# Mars.net
KiCad netlist of a schematic drawn in EAGLE
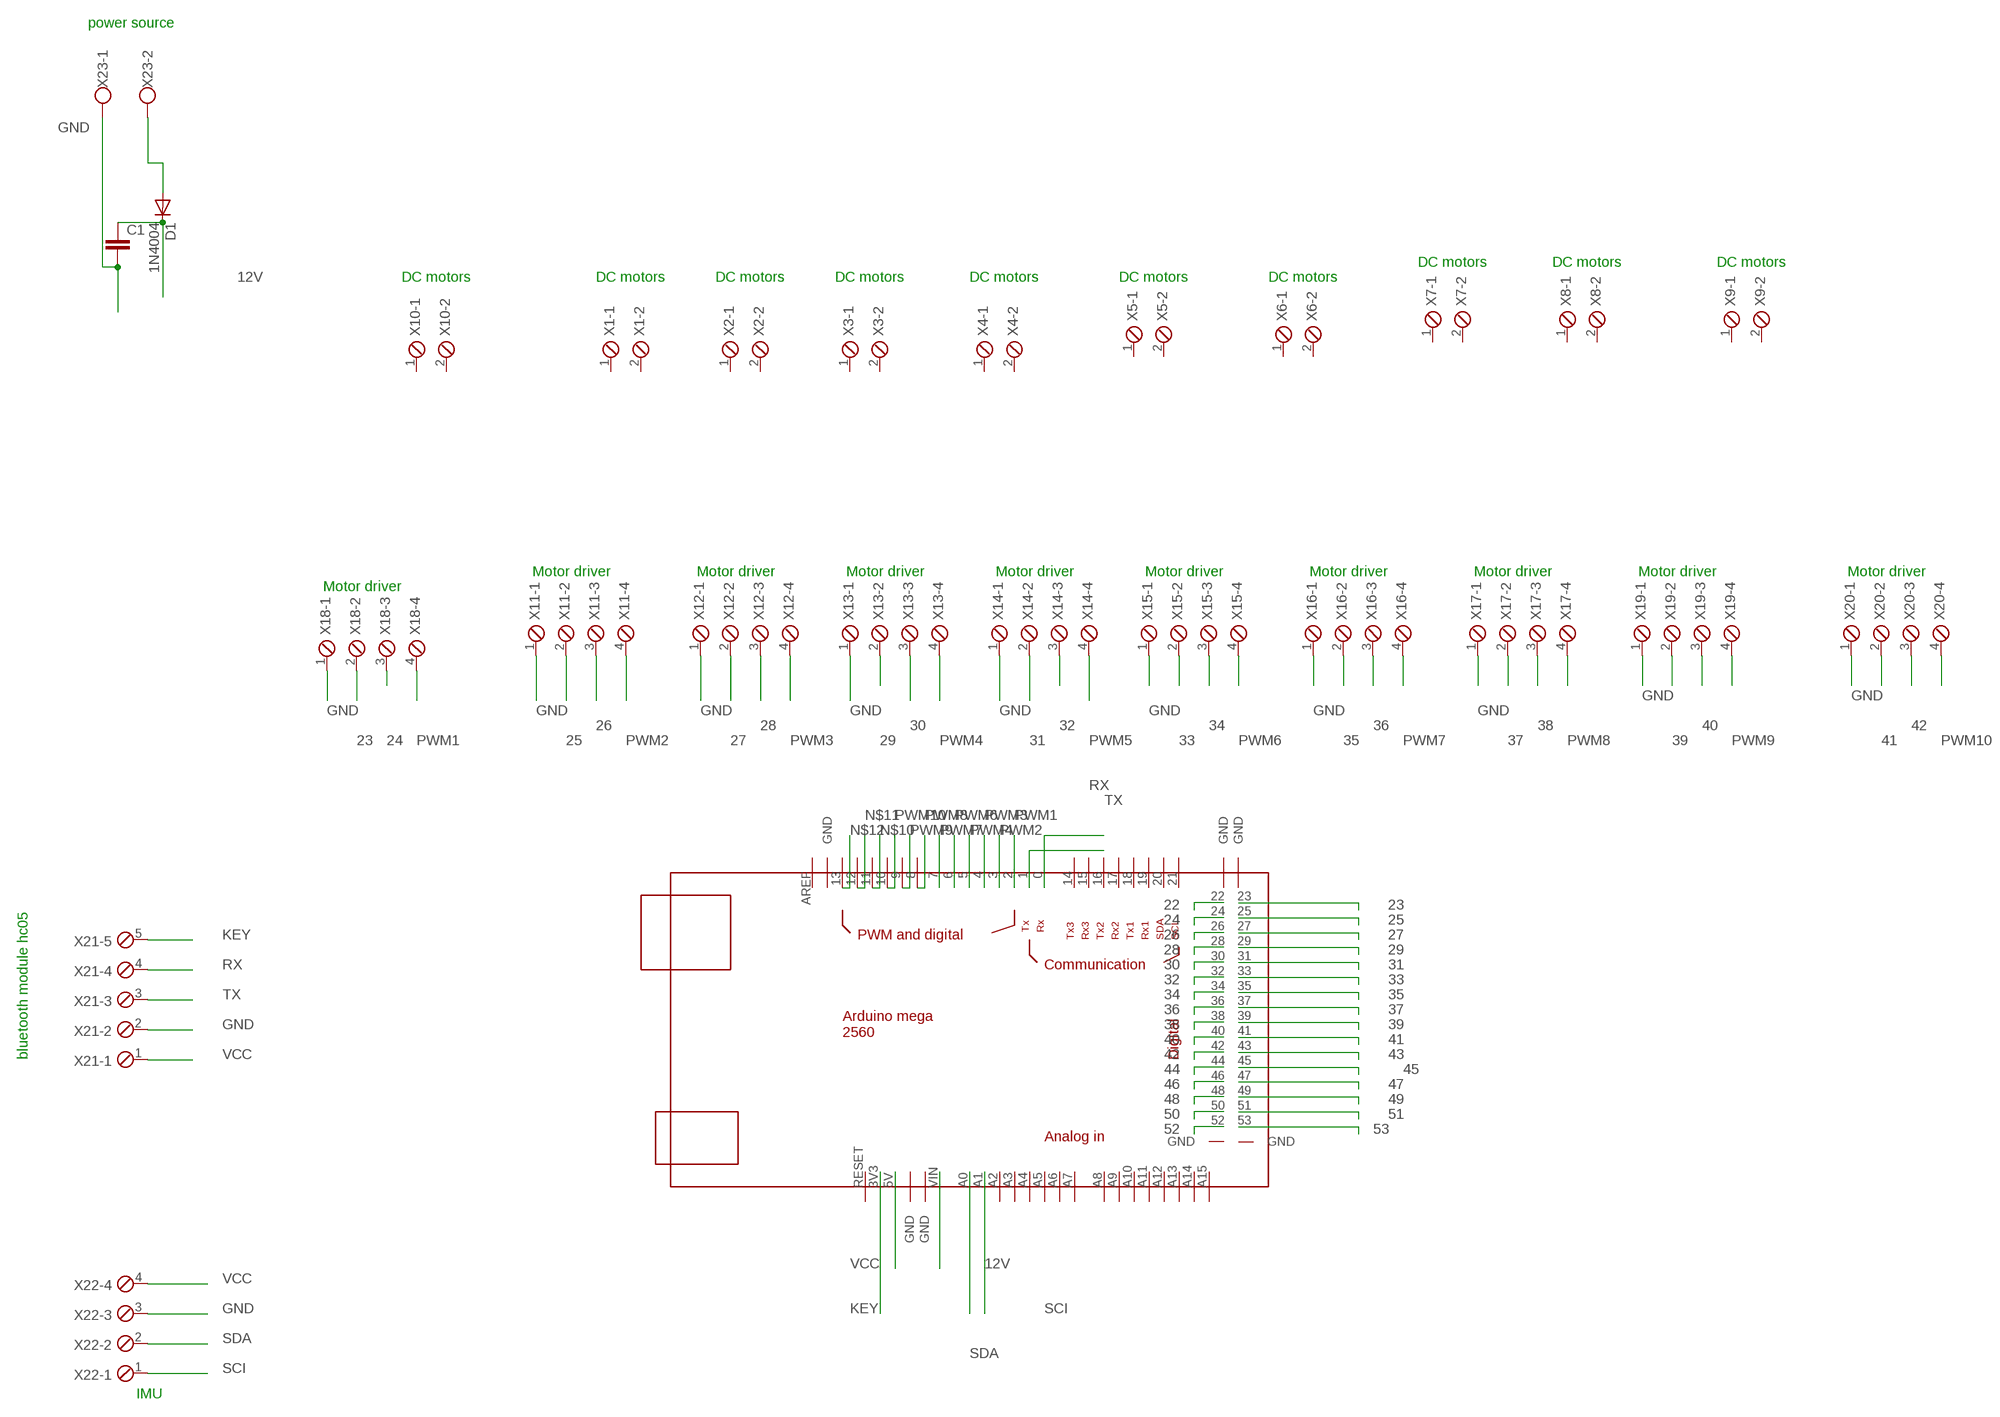
[diagram p0: schematic, sheet 1]

(export (version "E")
  (design (tool "Eeschema 10.0.6"))
  (components
    (comp (ref "C1")
      (value "C-EU025-025X050")
      (footprint "eagle-import:C025-025X050")
      (libsource (lib "eagle-import") (part "C-EU025-025X050"))
    )
    (comp (ref "D1")
      (value "1N4004")
      (footprint "eagle-import:DO41-10")
      (libsource (lib "eagle-import") (part "1N4004"))
    )
    (comp (ref "U$1")
      (value "MEGA_DEVICE")
      (footprint "eagle-import:MEGABOX")
      (libsource (lib "eagle-import") (part "MEGA_DEVICE"))
    )
    (comp (ref "X1")
      (value "MPT2")
      (footprint "eagle-import:2POL254")
      (libsource (lib "eagle-import") (part "MPT2"))
    )
    (comp (ref "X2")
      (value "MPT2")
      (footprint "eagle-import:2POL254")
      (libsource (lib "eagle-import") (part "MPT2"))
    )
    (comp (ref "X3")
      (value "MPT2")
      (footprint "eagle-import:2POL254")
      (libsource (lib "eagle-import") (part "MPT2"))
    )
    (comp (ref "X4")
      (value "MPT2")
      (footprint "eagle-import:2POL254")
      (libsource (lib "eagle-import") (part "MPT2"))
    )
    (comp (ref "X5")
      (value "MPT2")
      (footprint "eagle-import:2POL254")
      (libsource (lib "eagle-import") (part "MPT2"))
    )
    (comp (ref "X6")
      (value "MPT2")
      (footprint "eagle-import:2POL254")
      (libsource (lib "eagle-import") (part "MPT2"))
    )
    (comp (ref "X7")
      (value "MPT2")
      (footprint "eagle-import:2POL254")
      (libsource (lib "eagle-import") (part "MPT2"))
    )
    (comp (ref "X8")
      (value "MPT2")
      (footprint "eagle-import:2POL254")
      (libsource (lib "eagle-import") (part "MPT2"))
    )
    (comp (ref "X9")
      (value "MPT2")
      (footprint "eagle-import:2POL254")
      (libsource (lib "eagle-import") (part "MPT2"))
    )
    (comp (ref "X10")
      (value "MPT2")
      (footprint "eagle-import:2POL254")
      (libsource (lib "eagle-import") (part "MPT2"))
    )
    (comp (ref "X11")
      (value "MPT4")
      (footprint "eagle-import:4POL254")
      (libsource (lib "eagle-import") (part "MPT4"))
    )
    (comp (ref "X12")
      (value "MPT4")
      (footprint "eagle-import:4POL254")
      (libsource (lib "eagle-import") (part "MPT4"))
    )
    (comp (ref "X13")
      (value "MPT4")
      (footprint "eagle-import:4POL254")
      (libsource (lib "eagle-import") (part "MPT4"))
    )
    (comp (ref "X14")
      (value "MPT4")
      (footprint "eagle-import:4POL254")
      (libsource (lib "eagle-import") (part "MPT4"))
    )
    (comp (ref "X15")
      (value "MPT4")
      (footprint "eagle-import:4POL254")
      (libsource (lib "eagle-import") (part "MPT4"))
    )
    (comp (ref "X16")
      (value "MPT4")
      (footprint "eagle-import:4POL254")
      (libsource (lib "eagle-import") (part "MPT4"))
    )
    (comp (ref "X17")
      (value "MPT4")
      (footprint "eagle-import:4POL254")
      (libsource (lib "eagle-import") (part "MPT4"))
    )
    (comp (ref "X18")
      (value "MPT4")
      (footprint "eagle-import:4POL254")
      (libsource (lib "eagle-import") (part "MPT4"))
    )
    (comp (ref "X19")
      (value "MPT4")
      (footprint "eagle-import:4POL254")
      (libsource (lib "eagle-import") (part "MPT4"))
    )
    (comp (ref "X20")
      (value "MPT4")
      (footprint "eagle-import:4POL254")
      (libsource (lib "eagle-import") (part "MPT4"))
    )
    (comp (ref "X21")
      (value "MPT5")
      (footprint "eagle-import:5POL254")
      (libsource (lib "eagle-import") (part "MPT5"))
    )
    (comp (ref "X22")
      (value "MPT4")
      (footprint "eagle-import:4POL254")
      (libsource (lib "eagle-import") (part "MPT4"))
    )
    (comp (ref "X23")
      (value "W237-113")
      (footprint "eagle-import:W237-113")
      (libsource (lib "eagle-import") (part "W237-113"))
    )
  )
  (nets
    (net (code "1") (name "/12V") (class "Default")
      (node (ref "C1") (pin "1") (pinfunction "1_1") (pintype "passive"))
      (node (ref "D1") (pin "A") (pinfunction "A_A") (pintype "passive"))
      (node (ref "D1") (pin "C") (pinfunction "C_C") (pintype "passive"))
      (node (ref "U$1") (pin "VIN") (pinfunction "VIN_VIN") (pintype "bidirectional"))
      (node (ref "X23") (pin "2") (pinfunction "KL_2") (pintype "passive"))
    )
    (net (code "2") (name "/22") (class "Default")
      (node (ref "U$1") (pin "22") (pinfunction "22_22") (pintype "bidirectional"))
    )
    (net (code "3") (name "/23") (class "Default")
      (node (ref "U$1") (pin "23") (pinfunction "23_23") (pintype "bidirectional"))
      (node (ref "X18") (pin "2") (pinfunction "1_2") (pintype "passive"))
    )
    (net (code "4") (name "/24") (class "Default")
      (node (ref "U$1") (pin "24") (pinfunction "24_24") (pintype "bidirectional"))
      (node (ref "X18") (pin "3") (pinfunction "1_3") (pintype "passive"))
    )
    (net (code "5") (name "/25") (class "Default")
      (node (ref "U$1") (pin "25") (pinfunction "25_25") (pintype "bidirectional"))
      (node (ref "X11") (pin "2") (pinfunction "1_2") (pintype "passive"))
    )
    (net (code "6") (name "/26") (class "Default")
      (node (ref "U$1") (pin "26") (pinfunction "26_26") (pintype "bidirectional"))
      (node (ref "X11") (pin "3") (pinfunction "1_3") (pintype "passive"))
    )
    (net (code "7") (name "/27") (class "Default")
      (node (ref "U$1") (pin "27") (pinfunction "27_27") (pintype "bidirectional"))
      (node (ref "X12") (pin "2") (pinfunction "1_2") (pintype "passive"))
    )
    (net (code "8") (name "/28") (class "Default")
      (node (ref "U$1") (pin "28") (pinfunction "28_28") (pintype "bidirectional"))
      (node (ref "X12") (pin "3") (pinfunction "1_3") (pintype "passive"))
    )
    (net (code "9") (name "/29") (class "Default")
      (node (ref "U$1") (pin "29") (pinfunction "29_29") (pintype "bidirectional"))
      (node (ref "X13") (pin "2") (pinfunction "1_2") (pintype "passive"))
    )
    (net (code "10") (name "/30") (class "Default")
      (node (ref "U$1") (pin "30") (pinfunction "30_30") (pintype "bidirectional"))
      (node (ref "X13") (pin "3") (pinfunction "1_3") (pintype "passive"))
    )
    (net (code "11") (name "/31") (class "Default")
      (node (ref "U$1") (pin "31") (pinfunction "31_31") (pintype "bidirectional"))
      (node (ref "X14") (pin "2") (pinfunction "1_2") (pintype "passive"))
    )
    (net (code "12") (name "/32") (class "Default")
      (node (ref "U$1") (pin "32") (pinfunction "32_32") (pintype "bidirectional"))
      (node (ref "X14") (pin "3") (pinfunction "1_3") (pintype "passive"))
    )
    (net (code "13") (name "/33") (class "Default")
      (node (ref "U$1") (pin "33") (pinfunction "33_33") (pintype "bidirectional"))
      (node (ref "X15") (pin "2") (pinfunction "1_2") (pintype "passive"))
    )
    (net (code "14") (name "/34") (class "Default")
      (node (ref "U$1") (pin "34") (pinfunction "34_34") (pintype "bidirectional"))
      (node (ref "X15") (pin "3") (pinfunction "1_3") (pintype "passive"))
    )
    (net (code "15") (name "/35") (class "Default")
      (node (ref "U$1") (pin "35") (pinfunction "35_35") (pintype "bidirectional"))
      (node (ref "X16") (pin "2") (pinfunction "1_2") (pintype "passive"))
    )
    (net (code "16") (name "/36") (class "Default")
      (node (ref "U$1") (pin "36") (pinfunction "36_36") (pintype "bidirectional"))
      (node (ref "X16") (pin "3") (pinfunction "1_3") (pintype "passive"))
    )
    (net (code "17") (name "/37") (class "Default")
      (node (ref "U$1") (pin "37") (pinfunction "37_37") (pintype "bidirectional"))
      (node (ref "X17") (pin "2") (pinfunction "1_2") (pintype "passive"))
    )
    (net (code "18") (name "/38") (class "Default")
      (node (ref "U$1") (pin "38") (pinfunction "38_38") (pintype "bidirectional"))
      (node (ref "X17") (pin "3") (pinfunction "1_3") (pintype "passive"))
    )
    (net (code "19") (name "/39") (class "Default")
      (node (ref "U$1") (pin "39") (pinfunction "39_39") (pintype "bidirectional"))
      (node (ref "X19") (pin "2") (pinfunction "1_2") (pintype "passive"))
    )
    (net (code "20") (name "/40") (class "Default")
      (node (ref "U$1") (pin "40") (pinfunction "40_40") (pintype "bidirectional"))
      (node (ref "X19") (pin "3") (pinfunction "1_3") (pintype "passive"))
    )
    (net (code "21") (name "/41") (class "Default")
      (node (ref "U$1") (pin "41") (pinfunction "41_41") (pintype "bidirectional"))
      (node (ref "X20") (pin "2") (pinfunction "1_2") (pintype "passive"))
    )
    (net (code "22") (name "/42") (class "Default")
      (node (ref "U$1") (pin "42") (pinfunction "42_42") (pintype "bidirectional"))
      (node (ref "X20") (pin "3") (pinfunction "1_3") (pintype "passive"))
    )
    (net (code "23") (name "/43") (class "Default")
      (node (ref "U$1") (pin "43") (pinfunction "43_43") (pintype "bidirectional"))
    )
    (net (code "24") (name "/44") (class "Default")
      (node (ref "U$1") (pin "44") (pinfunction "44_44") (pintype "bidirectional"))
    )
    (net (code "25") (name "/45") (class "Default")
      (node (ref "U$1") (pin "45") (pinfunction "45_45") (pintype "bidirectional"))
    )
    (net (code "26") (name "/46") (class "Default")
      (node (ref "U$1") (pin "46") (pinfunction "46_46") (pintype "bidirectional"))
    )
    (net (code "27") (name "/47") (class "Default")
      (node (ref "U$1") (pin "47") (pinfunction "47_47") (pintype "bidirectional"))
    )
    (net (code "28") (name "/48") (class "Default")
      (node (ref "U$1") (pin "48") (pinfunction "48_48") (pintype "bidirectional"))
    )
    (net (code "29") (name "/49") (class "Default")
      (node (ref "U$1") (pin "49") (pinfunction "49_49") (pintype "bidirectional"))
    )
    (net (code "30") (name "/50") (class "Default")
      (node (ref "U$1") (pin "50") (pinfunction "50_50") (pintype "bidirectional"))
    )
    (net (code "31") (name "/51") (class "Default")
      (node (ref "U$1") (pin "51") (pinfunction "51_51") (pintype "bidirectional"))
    )
    (net (code "32") (name "/52") (class "Default")
      (node (ref "U$1") (pin "52") (pinfunction "52_52") (pintype "bidirectional"))
    )
    (net (code "33") (name "/53") (class "Default")
      (node (ref "U$1") (pin "53") (pinfunction "53_53") (pintype "bidirectional"))
    )
    (net (code "34") (name "/GND") (class "Default")
      (node (ref "C1") (pin "2") (pinfunction "2_2") (pintype "passive"))
      (node (ref "X11") (pin "1") (pinfunction "1_1") (pintype "passive"))
      (node (ref "X12") (pin "1") (pinfunction "1_1") (pintype "passive"))
      (node (ref "X13") (pin "1") (pinfunction "1_1") (pintype "passive"))
      (node (ref "X14") (pin "1") (pinfunction "1_1") (pintype "passive"))
      (node (ref "X15") (pin "1") (pinfunction "1_1") (pintype "passive"))
      (node (ref "X16") (pin "1") (pinfunction "1_1") (pintype "passive"))
      (node (ref "X17") (pin "1") (pinfunction "1_1") (pintype "passive"))
      (node (ref "X18") (pin "1") (pinfunction "1_1") (pintype "passive"))
      (node (ref "X19") (pin "1") (pinfunction "1_1") (pintype "passive"))
      (node (ref "X20") (pin "1") (pinfunction "1_1") (pintype "passive"))
      (node (ref "X21") (pin "2") (pinfunction "1_2") (pintype "passive"))
      (node (ref "X22") (pin "3") (pinfunction "1_3") (pintype "passive"))
      (node (ref "X23") (pin "1") (pinfunction "KL_1") (pintype "passive"))
    )
    (net (code "35") (name "/KEY") (class "Default")
      (node (ref "U$1") (pin "3V3") (pinfunction "3V3_3V3") (pintype "bidirectional"))
      (node (ref "X21") (pin "5") (pinfunction "1_5") (pintype "passive"))
    )
    (net (code "36") (name "/N$10") (class "Default")
      (node (ref "U$1") (pin "11") (pinfunction "11_11") (pintype "bidirectional"))
    )
    (net (code "37") (name "/N$11") (class "Default")
      (node (ref "U$1") (pin "12") (pinfunction "12_12") (pintype "bidirectional"))
    )
    (net (code "38") (name "/N$12") (class "Default")
      (node (ref "U$1") (pin "13") (pinfunction "13_13") (pintype "bidirectional"))
    )
    (net (code "39") (name "/PWM1") (class "Default")
      (node (ref "U$1") (pin "2") (pinfunction "2_2") (pintype "bidirectional"))
      (node (ref "X18") (pin "4") (pinfunction "1_4") (pintype "passive"))
    )
    (net (code "40") (name "/PWM2") (class "Default")
      (node (ref "U$1") (pin "3") (pinfunction "3_3") (pintype "bidirectional"))
      (node (ref "X11") (pin "4") (pinfunction "1_4") (pintype "passive"))
    )
    (net (code "41") (name "/PWM3") (class "Default")
      (node (ref "U$1") (pin "4") (pinfunction "4_4") (pintype "bidirectional"))
      (node (ref "X12") (pin "4") (pinfunction "1_4") (pintype "passive"))
    )
    (net (code "42") (name "/PWM4") (class "Default")
      (node (ref "U$1") (pin "5") (pinfunction "5_5") (pintype "bidirectional"))
      (node (ref "X13") (pin "4") (pinfunction "1_4") (pintype "passive"))
    )
    (net (code "43") (name "/PWM5") (class "Default")
      (node (ref "X14") (pin "4") (pinfunction "1_4") (pintype "passive"))
    )
    (net (code "44") (name "/PWM6") (class "Default")
      (node (ref "U$1") (pin "6") (pinfunction "6_6") (pintype "bidirectional"))
      (node (ref "X15") (pin "4") (pinfunction "1_4") (pintype "passive"))
    )
    (net (code "45") (name "/PWM7") (class "Default")
      (node (ref "U$1") (pin "7") (pinfunction "7_7") (pintype "bidirectional"))
      (node (ref "X16") (pin "4") (pinfunction "1_4") (pintype "passive"))
    )
    (net (code "46") (name "/PWM8") (class "Default")
      (node (ref "U$1") (pin "8") (pinfunction "8_8") (pintype "bidirectional"))
      (node (ref "X17") (pin "4") (pinfunction "1_4") (pintype "passive"))
    )
    (net (code "47") (name "/PWM9") (class "Default")
      (node (ref "U$1") (pin "9") (pinfunction "9_9") (pintype "bidirectional"))
      (node (ref "X19") (pin "4") (pinfunction "1_4") (pintype "passive"))
    )
    (net (code "48") (name "/PWM10") (class "Default")
      (node (ref "U$1") (pin "10") (pinfunction "10_10") (pintype "bidirectional"))
      (node (ref "X20") (pin "4") (pinfunction "1_4") (pintype "passive"))
    )
    (net (code "49") (name "/RX") (class "Default")
      (node (ref "U$1") (pin "1") (pinfunction "1_1") (pintype "bidirectional"))
      (node (ref "X21") (pin "4") (pinfunction "1_4") (pintype "passive"))
    )
    (net (code "50") (name "/SCI") (class "Default")
      (node (ref "U$1") (pin "A1") (pinfunction "A1_A1") (pintype "bidirectional"))
      (node (ref "X22") (pin "1") (pinfunction "1_1") (pintype "passive"))
    )
    (net (code "51") (name "/SDA") (class "Default")
      (node (ref "U$1") (pin "A0") (pinfunction "A0_A0") (pintype "bidirectional"))
      (node (ref "X22") (pin "2") (pinfunction "1_2") (pintype "passive"))
    )
    (net (code "52") (name "/TX") (class "Default")
      (node (ref "U$1") (pin "0") (pinfunction "0_0") (pintype "bidirectional"))
      (node (ref "X21") (pin "3") (pinfunction "1_3") (pintype "passive"))
    )
    (net (code "53") (name "/VCC") (class "Default")
      (node (ref "U$1") (pin "5V") (pinfunction "5V_5V") (pintype "bidirectional"))
      (node (ref "X21") (pin "1") (pinfunction "1_1") (pintype "passive"))
      (node (ref "X22") (pin "4") (pinfunction "1_4") (pintype "passive"))
    )
    (net (code "54") (name "unconnected-(U$1-GND-PadGND@1)") (class "Default")
      (node (ref "U$1") (pin "GND@1") (pinfunction "GND_GND@1") (pintype "bidirectional"))
    )
    (net (code "55") (name "unconnected-(U$1-GND-PadGND@2)") (class "Default")
      (node (ref "U$1") (pin "GND@2") (pinfunction "GND_GND@2") (pintype "bidirectional"))
    )
    (net (code "56") (name "unconnected-(U$1-GND-PadGND@3)") (class "Default")
      (node (ref "U$1") (pin "GND@3") (pinfunction "GND_GND@3") (pintype "bidirectional"))
    )
    (net (code "57") (name "unconnected-(U$1-GND-PadGND@4)") (class "Default")
      (node (ref "U$1") (pin "GND@4") (pinfunction "GND_GND@4") (pintype "bidirectional"))
    )
    (net (code "58") (name "unconnected-(U$1-GND-PadGND@5)") (class "Default")
      (node (ref "U$1") (pin "GND@5") (pinfunction "GND_GND@5") (pintype "bidirectional"))
    )
    (net (code "59") (name "unconnected-(U$1-GND-PadGND@6)") (class "Default")
      (node (ref "U$1") (pin "GND@6") (pinfunction "GND_GND@6") (pintype "bidirectional"))
    )
    (net (code "60") (name "unconnected-(U$1-GND-PadGND@7)") (class "Default")
      (node (ref "U$1") (pin "GND@7") (pinfunction "GND_GND@7") (pintype "bidirectional"))
    )
    (net (code "61") (name "unconnected-(U$1-Pad14)") (class "Default")
      (node (ref "U$1") (pin "14") (pinfunction "14_14") (pintype "bidirectional"))
    )
    (net (code "62") (name "unconnected-(U$1-Pad15)") (class "Default")
      (node (ref "U$1") (pin "15") (pinfunction "15_15") (pintype "bidirectional"))
    )
    (net (code "63") (name "unconnected-(U$1-Pad16)") (class "Default")
      (node (ref "U$1") (pin "16") (pinfunction "16_16") (pintype "bidirectional"))
    )
    (net (code "64") (name "unconnected-(U$1-Pad17)") (class "Default")
      (node (ref "U$1") (pin "17") (pinfunction "17_17") (pintype "bidirectional"))
    )
    (net (code "65") (name "unconnected-(U$1-Pad18)") (class "Default")
      (node (ref "U$1") (pin "18") (pinfunction "18_18") (pintype "bidirectional"))
    )
    (net (code "66") (name "unconnected-(U$1-Pad19)") (class "Default")
      (node (ref "U$1") (pin "19") (pinfunction "19_19") (pintype "bidirectional"))
    )
    (net (code "67") (name "unconnected-(U$1-Pad20)") (class "Default")
      (node (ref "U$1") (pin "20") (pinfunction "20_20") (pintype "bidirectional"))
    )
    (net (code "68") (name "unconnected-(U$1-Pad21)") (class "Default")
      (node (ref "U$1") (pin "21") (pinfunction "21_21") (pintype "bidirectional"))
    )
    (net (code "69") (name "unconnected-(U$1-PadA2)") (class "Default")
      (node (ref "U$1") (pin "A2") (pinfunction "A2_A2") (pintype "bidirectional"))
    )
    (net (code "70") (name "unconnected-(U$1-PadA3)") (class "Default")
      (node (ref "U$1") (pin "A3") (pinfunction "A3_A3") (pintype "bidirectional"))
    )
    (net (code "71") (name "unconnected-(U$1-PadA4)") (class "Default")
      (node (ref "U$1") (pin "A4") (pinfunction "A4_A4") (pintype "bidirectional"))
    )
    (net (code "72") (name "unconnected-(U$1-PadA5)") (class "Default")
      (node (ref "U$1") (pin "A5") (pinfunction "A5_A5") (pintype "bidirectional"))
    )
    (net (code "73") (name "unconnected-(U$1-PadA6)") (class "Default")
      (node (ref "U$1") (pin "A6") (pinfunction "A6_A6") (pintype "bidirectional"))
    )
    (net (code "74") (name "unconnected-(U$1-PadA7)") (class "Default")
      (node (ref "U$1") (pin "A7") (pinfunction "A7_A7") (pintype "bidirectional"))
    )
    (net (code "75") (name "unconnected-(U$1-PadA8)") (class "Default")
      (node (ref "U$1") (pin "A8") (pinfunction "A8_A8") (pintype "bidirectional"))
    )
    (net (code "76") (name "unconnected-(U$1-PadA9)") (class "Default")
      (node (ref "U$1") (pin "A9") (pinfunction "A9_A9") (pintype "bidirectional"))
    )
    (net (code "77") (name "unconnected-(U$1-PadA10)") (class "Default")
      (node (ref "U$1") (pin "A10") (pinfunction "A10_A10") (pintype "bidirectional"))
    )
    (net (code "78") (name "unconnected-(U$1-PadA11)") (class "Default")
      (node (ref "U$1") (pin "A11") (pinfunction "A11_A11") (pintype "bidirectional"))
    )
    (net (code "79") (name "unconnected-(U$1-PadA12)") (class "Default")
      (node (ref "U$1") (pin "A12") (pinfunction "A12_A12") (pintype "bidirectional"))
    )
    (net (code "80") (name "unconnected-(U$1-PadA13)") (class "Default")
      (node (ref "U$1") (pin "A13") (pinfunction "A13_A13") (pintype "bidirectional"))
    )
    (net (code "81") (name "unconnected-(U$1-PadA14)") (class "Default")
      (node (ref "U$1") (pin "A14") (pinfunction "A14_A14") (pintype "bidirectional"))
    )
    (net (code "82") (name "unconnected-(U$1-PadA15)") (class "Default")
      (node (ref "U$1") (pin "A15") (pinfunction "A15_A15") (pintype "bidirectional"))
    )
    (net (code "83") (name "unconnected-(U$1-PadAREF)") (class "Default")
      (node (ref "U$1") (pin "AREF") (pinfunction "AREF_AREF") (pintype "bidirectional"))
    )
    (net (code "84") (name "unconnected-(U$1-PadRESET)") (class "Default")
      (node (ref "U$1") (pin "RESET") (pinfunction "RESET_RESET") (pintype "bidirectional"))
    )
    (net (code "85") (name "unconnected-(X1-Pad1)") (class "Default")
      (node (ref "X1") (pin "1") (pinfunction "1_1") (pintype "passive"))
    )
    (net (code "86") (name "unconnected-(X1B-1-Pad2)") (class "Default")
      (node (ref "X1") (pin "2") (pinfunction "1_2") (pintype "passive"))
    )
    (net (code "87") (name "unconnected-(X2-Pad1)") (class "Default")
      (node (ref "X2") (pin "1") (pinfunction "1_1") (pintype "passive"))
    )
    (net (code "88") (name "unconnected-(X2B-1-Pad2)") (class "Default")
      (node (ref "X2") (pin "2") (pinfunction "1_2") (pintype "passive"))
    )
    (net (code "89") (name "unconnected-(X3-Pad1)") (class "Default")
      (node (ref "X3") (pin "1") (pinfunction "1_1") (pintype "passive"))
    )
    (net (code "90") (name "unconnected-(X3B-1-Pad2)") (class "Default")
      (node (ref "X3") (pin "2") (pinfunction "1_2") (pintype "passive"))
    )
    (net (code "91") (name "unconnected-(X4-Pad1)") (class "Default")
      (node (ref "X4") (pin "1") (pinfunction "1_1") (pintype "passive"))
    )
    (net (code "92") (name "unconnected-(X4B-1-Pad2)") (class "Default")
      (node (ref "X4") (pin "2") (pinfunction "1_2") (pintype "passive"))
    )
    (net (code "93") (name "unconnected-(X5-Pad1)") (class "Default")
      (node (ref "X5") (pin "1") (pinfunction "1_1") (pintype "passive"))
    )
    (net (code "94") (name "unconnected-(X5B-1-Pad2)") (class "Default")
      (node (ref "X5") (pin "2") (pinfunction "1_2") (pintype "passive"))
    )
    (net (code "95") (name "unconnected-(X6-Pad1)") (class "Default")
      (node (ref "X6") (pin "1") (pinfunction "1_1") (pintype "passive"))
    )
    (net (code "96") (name "unconnected-(X6B-1-Pad2)") (class "Default")
      (node (ref "X6") (pin "2") (pinfunction "1_2") (pintype "passive"))
    )
    (net (code "97") (name "unconnected-(X7-Pad1)") (class "Default")
      (node (ref "X7") (pin "1") (pinfunction "1_1") (pintype "passive"))
    )
    (net (code "98") (name "unconnected-(X7B-1-Pad2)") (class "Default")
      (node (ref "X7") (pin "2") (pinfunction "1_2") (pintype "passive"))
    )
    (net (code "99") (name "unconnected-(X8-Pad1)") (class "Default")
      (node (ref "X8") (pin "1") (pinfunction "1_1") (pintype "passive"))
    )
    (net (code "100") (name "unconnected-(X8B-1-Pad2)") (class "Default")
      (node (ref "X8") (pin "2") (pinfunction "1_2") (pintype "passive"))
    )
    (net (code "101") (name "unconnected-(X9-Pad1)") (class "Default")
      (node (ref "X9") (pin "1") (pinfunction "1_1") (pintype "passive"))
    )
    (net (code "102") (name "unconnected-(X9B-1-Pad2)") (class "Default")
      (node (ref "X9") (pin "2") (pinfunction "1_2") (pintype "passive"))
    )
    (net (code "103") (name "unconnected-(X10-Pad1)") (class "Default")
      (node (ref "X10") (pin "1") (pinfunction "1_1") (pintype "passive"))
    )
    (net (code "104") (name "unconnected-(X10B-1-Pad2)") (class "Default")
      (node (ref "X10") (pin "2") (pinfunction "1_2") (pintype "passive"))
    )
  )
)
